# blinky_5_0.net
KiCad netlist of a schematic drawn in EAGLE
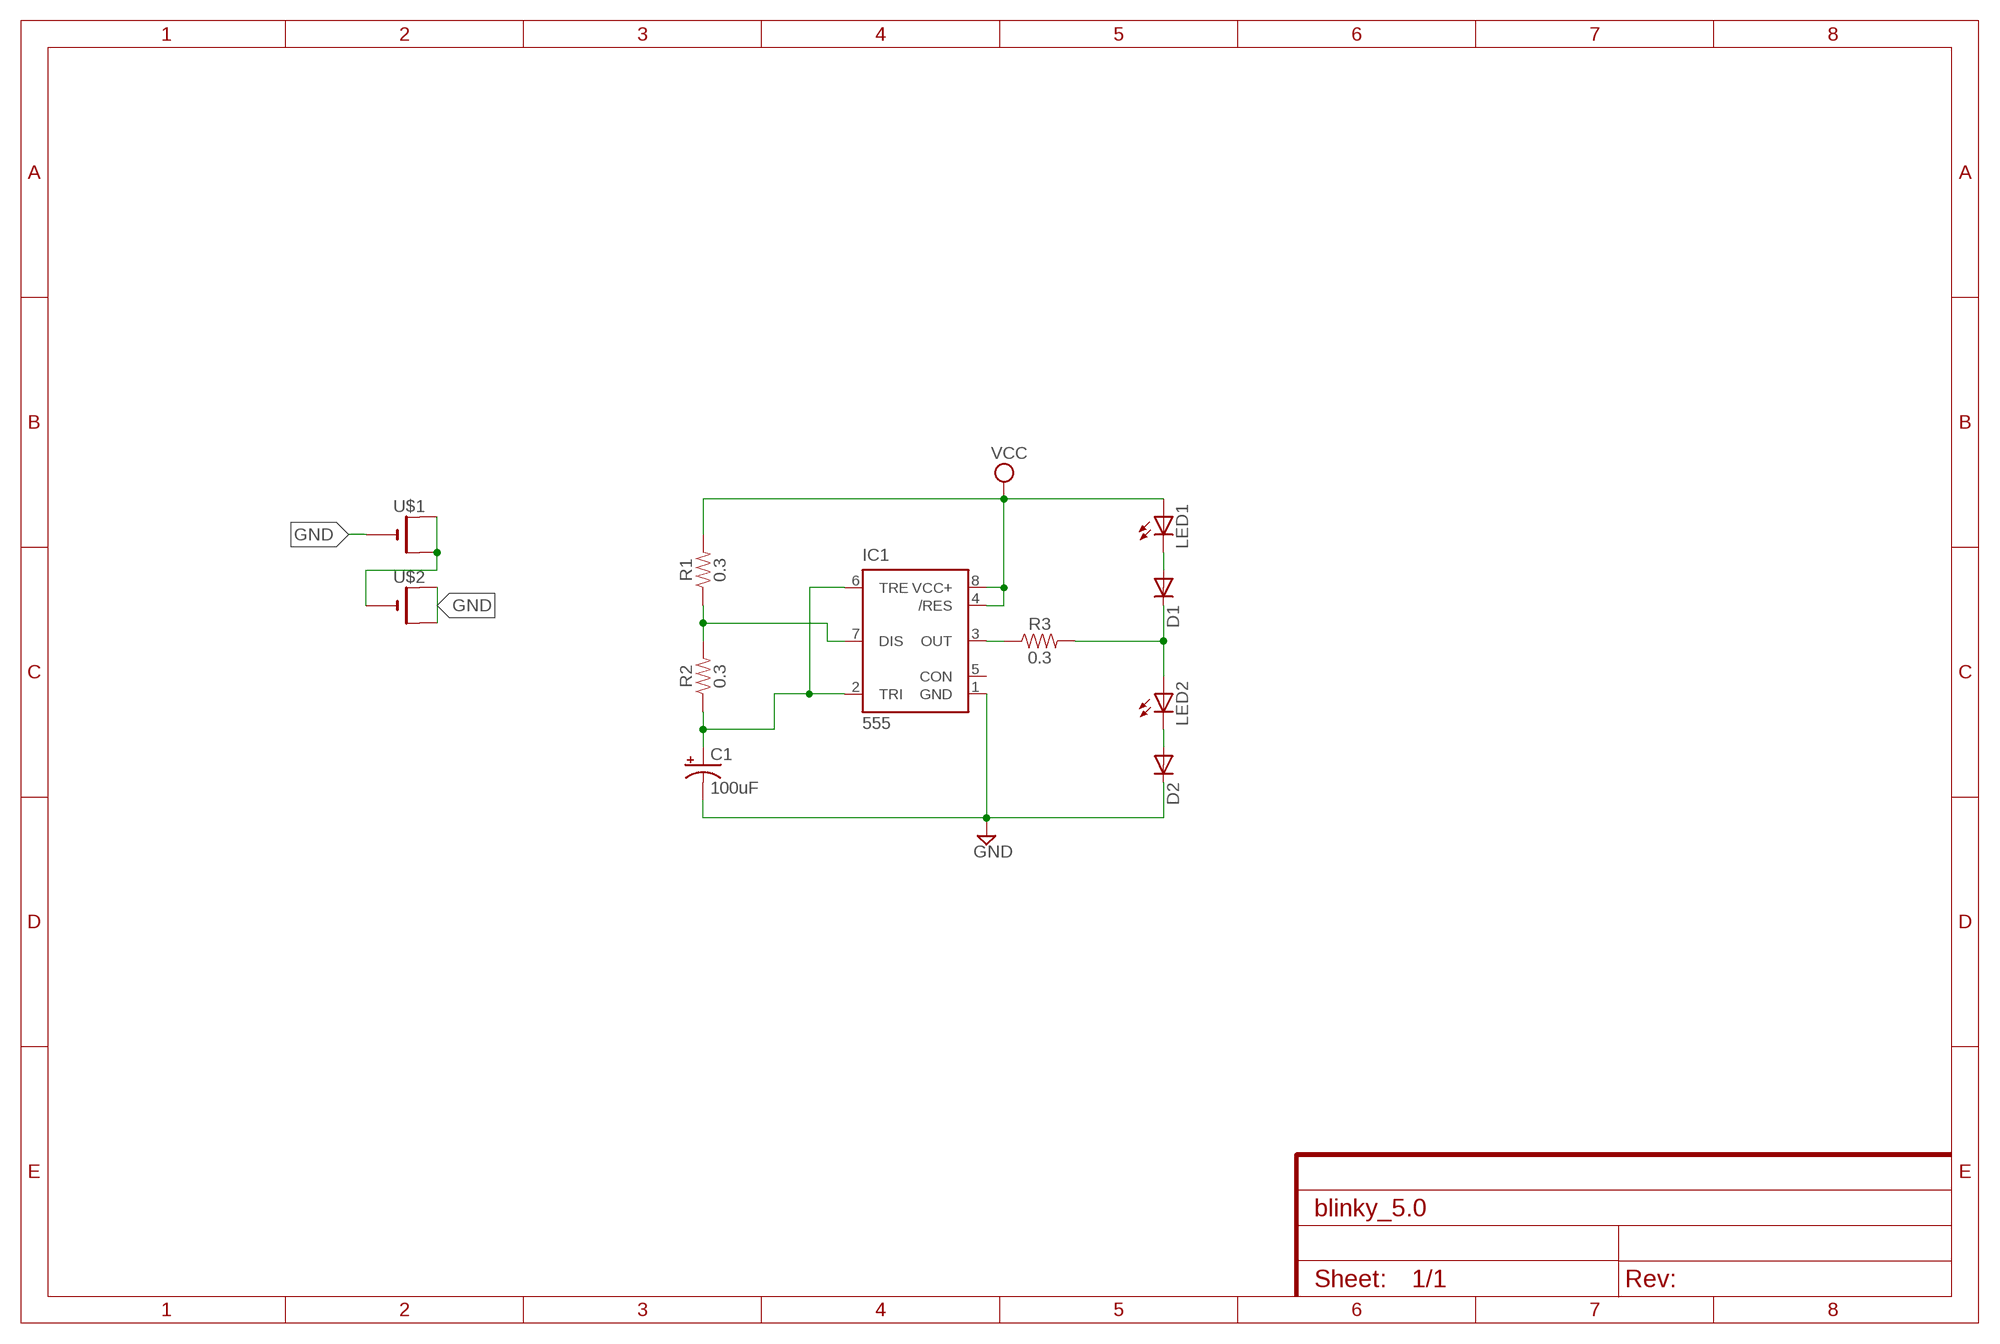
[diagram p0: schematic, sheet 1]

(export (version "E")
  (design (tool "Eeschema 10.0.6"))
  (components
    (comp (ref "C1")
      (value "100uF")
      (footprint "eagle-import:NIC_10X10.5_CAP")
      (libsource (lib "eagle-import") (part "100UF-POLAR-10X10.5-63V-20%"))
    )
    (comp (ref "D1")
      (value "1N4004")
      (footprint "eagle-import:DO41-10")
      (libsource (lib "eagle-import") (part "1N4004"))
    )
    (comp (ref "D2")
      (value "1N4004")
      (footprint "eagle-import:DO41-10")
      (libsource (lib "eagle-import") (part "1N4004"))
    )
    (comp (ref "IC1")
      (value "555")
      (footprint "eagle-import:SO08")
      (libsource (lib "eagle-import") (part "555D"))
    )
    (comp (ref "LED1")
      (value "LED5MM")
      (footprint "eagle-import:LED5MM")
      (libsource (lib "eagle-import") (part "LED5MM"))
    )
    (comp (ref "LED2")
      (value "LED5MM")
      (footprint "eagle-import:LED5MM")
      (libsource (lib "eagle-import") (part "LED5MM"))
    )
    (comp (ref "R1")
      (value "0.3")
      (footprint "eagle-import:0805")
      (libsource (lib "eagle-import") (part "0.3OHM-0805-1/8W-1%"))
    )
    (comp (ref "R2")
      (value "0.3")
      (footprint "eagle-import:0805")
      (libsource (lib "eagle-import") (part "0.3OHM-0805-1/8W-1%"))
    )
    (comp (ref "R3")
      (value "0.3")
      (footprint "eagle-import:0805")
      (libsource (lib "eagle-import") (part "0.3OHM-0805-1/8W-1%"))
    )
    (comp (ref "U$1")
      (value "CR1220SMT")
      (footprint "eagle-import:CR1220-SMD")
      (libsource (lib "eagle-import") (part "CR1220SMT"))
    )
    (comp (ref "U$2")
      (value "CR1220SMT")
      (footprint "eagle-import:CR1220-SMD")
      (libsource (lib "eagle-import") (part "CR1220SMT"))
    )
  )
  (nets
    (net (code "1") (name "GND") (class "Default")
      (node (ref "C1") (pin "-") (pinfunction "-_-") (pintype "passive"))
      (node (ref "D2") (pin "C") (pinfunction "C_C") (pintype "passive"))
      (node (ref "IC1") (pin "1") (pinfunction "GND_1") (pintype "power_in"))
      (node (ref "U$1") (pin "-") (pinfunction "-_-") (pintype "passive"))
      (node (ref "U$2") (pin "+$1") (pinfunction "+_+$1") (pintype "passive"))
      (node (ref "U$2") (pin "+$2") (pinfunction "+1_+$2") (pintype "passive"))
    )
    (net (code "2") (name "Net-(D1-PadC)") (class "Default")
      (node (ref "D1") (pin "C") (pinfunction "C_C") (pintype "passive"))
      (node (ref "LED2") (pin "A") (pinfunction "A_A") (pintype "passive"))
      (node (ref "R3") (pin "2") (pinfunction "2_2") (pintype "passive"))
    )
    (net (code "3") (name "Net-(IC1-DIS)") (class "Default")
      (node (ref "IC1") (pin "7") (pinfunction "DIS_7") (pintype "input"))
      (node (ref "R1") (pin "1") (pinfunction "1_1") (pintype "passive"))
      (node (ref "R2") (pin "2") (pinfunction "2_2") (pintype "passive"))
    )
    (net (code "4") (name "Net-(IC1-OUT)") (class "Default")
      (node (ref "IC1") (pin "3") (pinfunction "OUT_3") (pintype "output"))
      (node (ref "R3") (pin "1") (pinfunction "1_1") (pintype "passive"))
    )
    (net (code "5") (name "Net-(IC1-TRE)") (class "Default")
      (node (ref "C1") (pin "+") (pinfunction "+_+") (pintype "passive"))
      (node (ref "IC1") (pin "2") (pinfunction "TRI_2") (pintype "input"))
      (node (ref "IC1") (pin "6") (pinfunction "TRE_6") (pintype "input"))
      (node (ref "R2") (pin "1") (pinfunction "1_1") (pintype "passive"))
    )
    (net (code "6") (name "Net-(LED1-C)") (class "Default")
      (node (ref "D1") (pin "A") (pinfunction "A_A") (pintype "passive"))
      (node (ref "LED1") (pin "K") (pinfunction "C_K") (pintype "passive"))
    )
    (net (code "7") (name "Net-(LED2-C)") (class "Default")
      (node (ref "D2") (pin "A") (pinfunction "A_A") (pintype "passive"))
      (node (ref "LED2") (pin "K") (pinfunction "C_K") (pintype "passive"))
    )
    (net (code "8") (name "Net-(U$1-+)") (class "Default")
      (node (ref "U$1") (pin "+$1") (pinfunction "+_+$1") (pintype "passive"))
      (node (ref "U$1") (pin "+$2") (pinfunction "+1_+$2") (pintype "passive"))
      (node (ref "U$2") (pin "-") (pinfunction "-_-") (pintype "passive"))
    )
    (net (code "9") (name "VCC") (class "Default")
      (node (ref "IC1") (pin "4") (pinfunction "/RES_4") (pintype "input"))
      (node (ref "IC1") (pin "8") (pinfunction "VCC+_8") (pintype "power_in"))
      (node (ref "LED1") (pin "A") (pinfunction "A_A") (pintype "passive"))
      (node (ref "R1") (pin "2") (pinfunction "2_2") (pintype "passive"))
    )
    (net (code "10") (name "unconnected-(IC1-CON-Pad5)") (class "Default")
      (node (ref "IC1") (pin "5") (pinfunction "CON_5") (pintype "input"))
    )
  )
)
